# Main_DMB-4773-opto.net
KiCad netlist of a schematic drawn in EAGLE
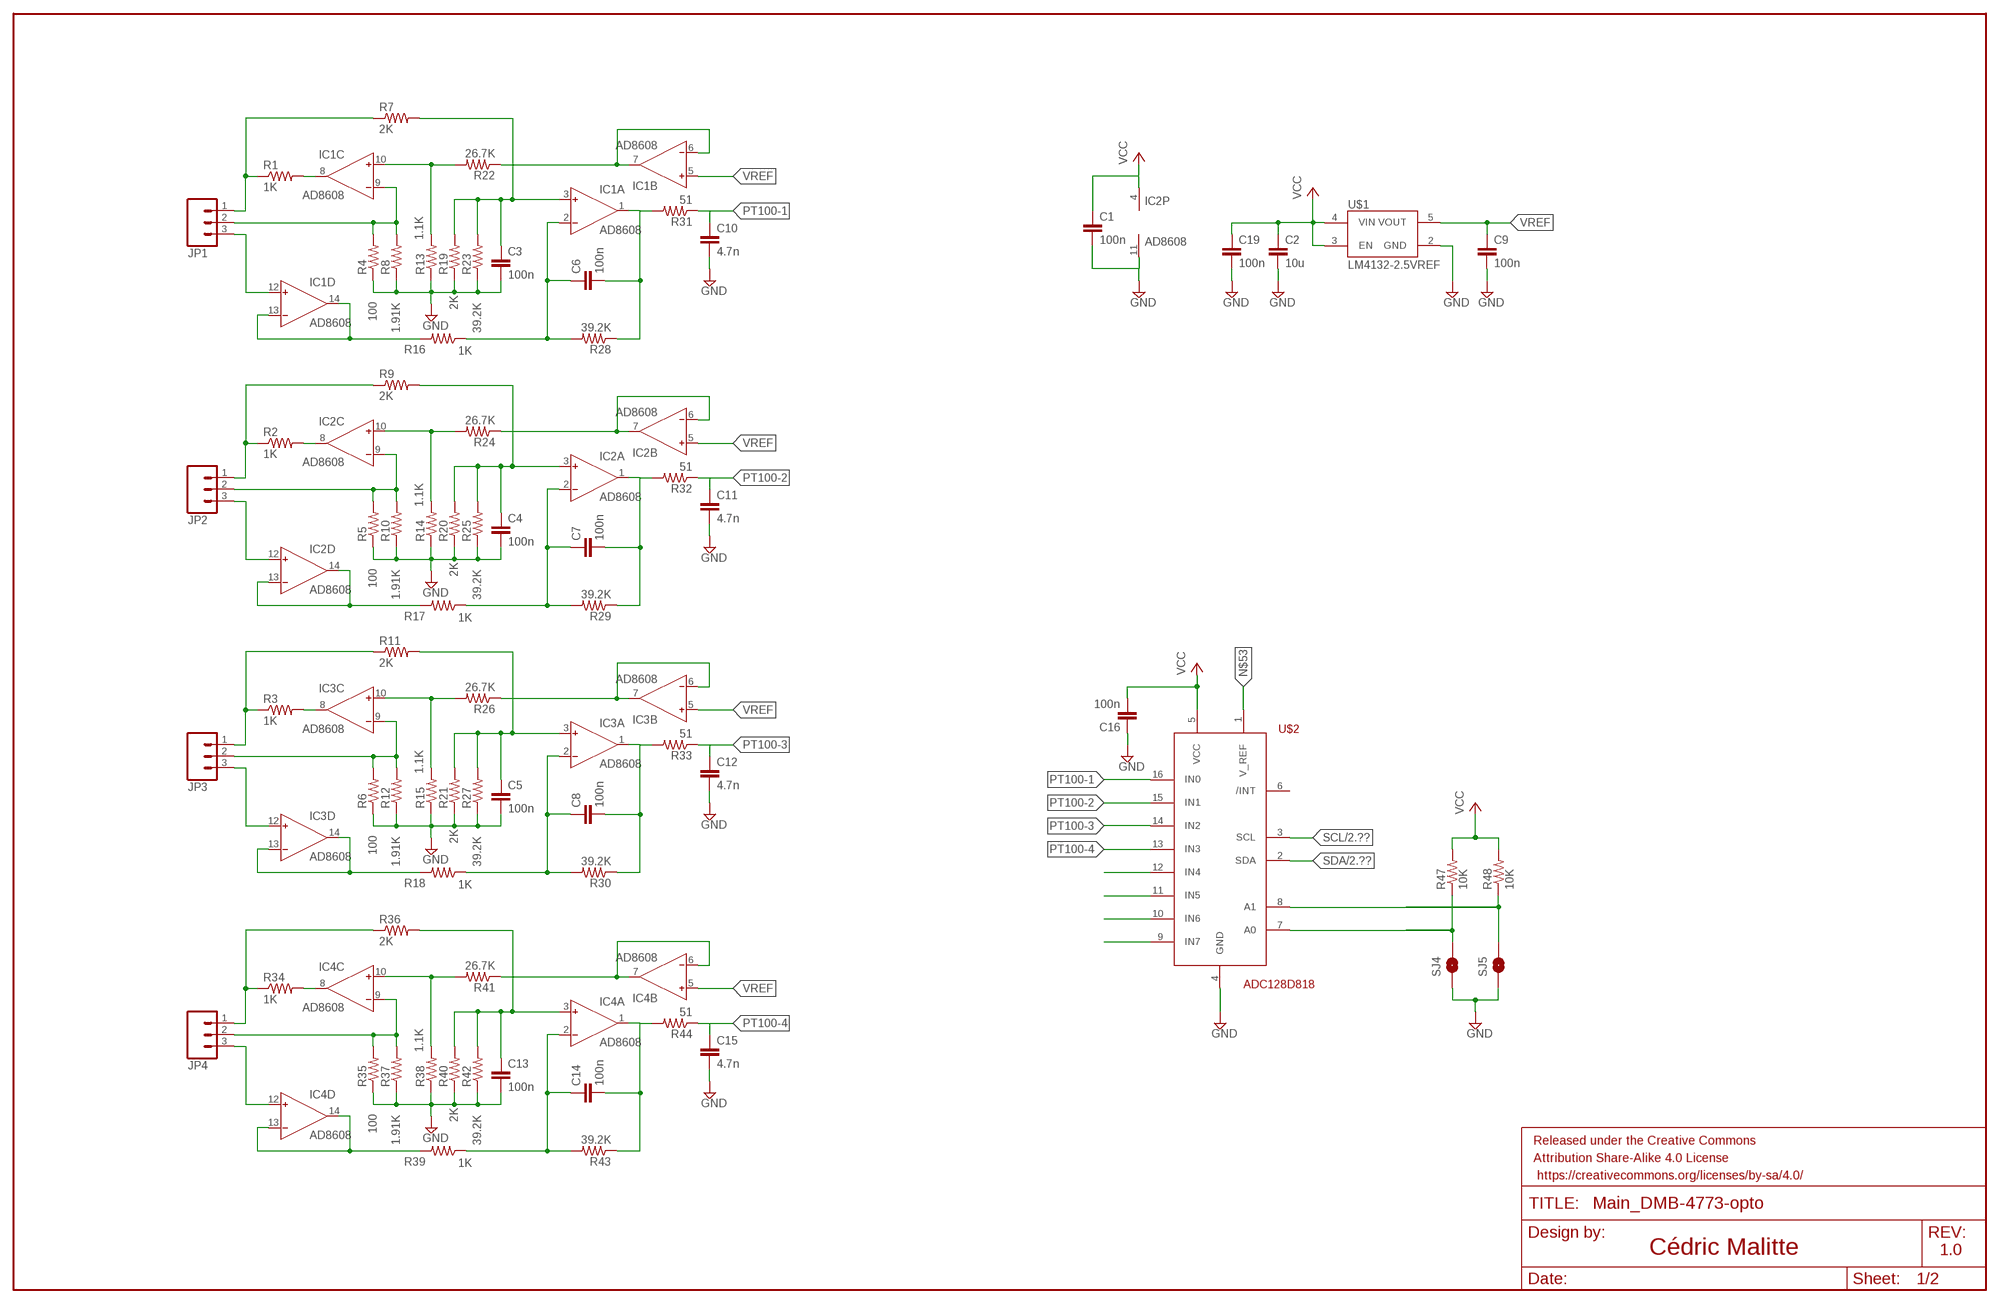
[diagram p0: schematic, sheet 1]
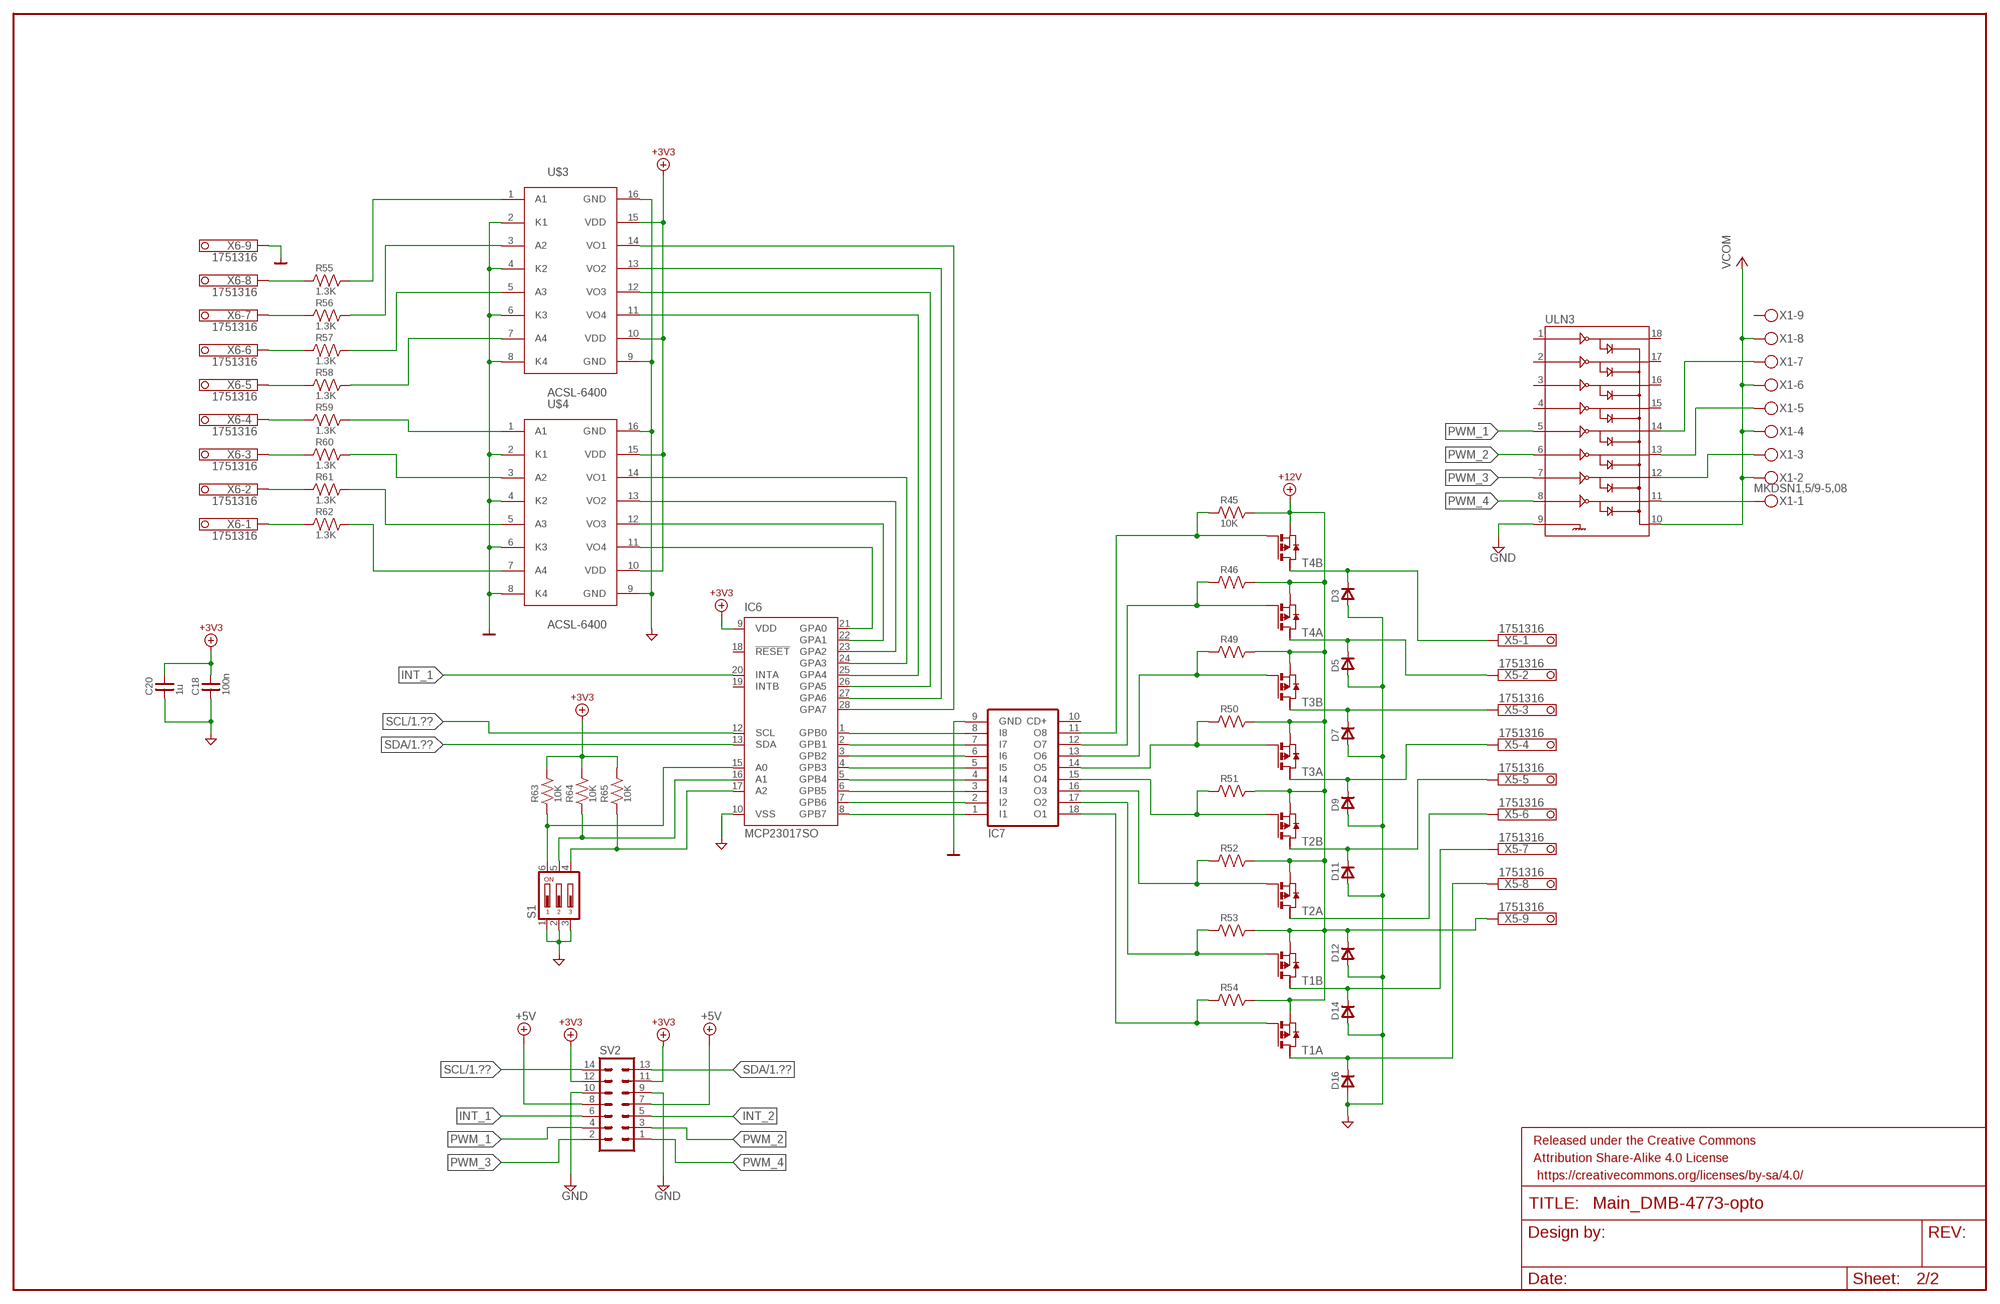
[diagram p1: schematic, sheet 2]

(export (version "E")
  (design (tool "Eeschema 10.0.6"))
  (components
    (comp (ref "C18")
      (value "100n")
      (footprint "eagle-import:C0805")
      (libsource (lib "eagle-import") (part "C0805"))
    )
    (comp (ref "C20")
      (value "1u")
      (footprint "eagle-import:C0805")
      (libsource (lib "eagle-import") (part "C0805"))
    )
    (comp (ref "D3")
      (value "DSMA")
      (footprint "eagle-import:DSMA")
      (libsource (lib "eagle-import") (part "DSMA"))
    )
    (comp (ref "D5")
      (value "DSMA")
      (footprint "eagle-import:DSMA")
      (libsource (lib "eagle-import") (part "DSMA"))
    )
    (comp (ref "D7")
      (value "DSMA")
      (footprint "eagle-import:DSMA")
      (libsource (lib "eagle-import") (part "DSMA"))
    )
    (comp (ref "D9")
      (value "DSMA")
      (footprint "eagle-import:DSMA")
      (libsource (lib "eagle-import") (part "DSMA"))
    )
    (comp (ref "D11")
      (value "DSMA")
      (footprint "eagle-import:DSMA")
      (libsource (lib "eagle-import") (part "DSMA"))
    )
    (comp (ref "D12")
      (value "DSMA")
      (footprint "eagle-import:DSMA")
      (libsource (lib "eagle-import") (part "DSMA"))
    )
    (comp (ref "D14")
      (value "DSMA")
      (footprint "eagle-import:DSMA")
      (libsource (lib "eagle-import") (part "DSMA"))
    )
    (comp (ref "D16")
      (value "DSMA")
      (footprint "eagle-import:DSMA")
      (libsource (lib "eagle-import") (part "DSMA"))
    )
    (comp (ref "FRAME3")
      (value "FRAME-LEDGER")
      (footprint "eagle-import:CREATIVE_COMMONS")
      (libsource (lib "eagle-import") (part "FRAME-LEDGER"))
    )
    (comp (ref "IC6")
      (value "MCP23017SO")
      (footprint "eagle-import:SO28W")
      (fields (field (name "MF") "MICROCHIP") (field (name "MPN") "MCP23017-E/SO"))
      (libsource (lib "eagle-import") (part "MCP23017SO"))
    )
    (comp (ref "IC7")
      (value "ULN2803A")
      (footprint "eagle-import:DIL18")
      (libsource (lib "eagle-import") (part "ULN2803A"))
    )
    (comp (ref "R45")
      (value "10K")
      (footprint "eagle-import:R0805")
      (libsource (lib "eagle-import") (part "RU0805"))
    )
    (comp (ref "R46")
      (value "RU0805")
      (footprint "eagle-import:R0805")
      (libsource (lib "eagle-import") (part "RU0805"))
    )
    (comp (ref "R49")
      (value "RU0805")
      (footprint "eagle-import:R0805")
      (libsource (lib "eagle-import") (part "RU0805"))
    )
    (comp (ref "R50")
      (value "RU0805")
      (footprint "eagle-import:R0805")
      (libsource (lib "eagle-import") (part "RU0805"))
    )
    (comp (ref "R51")
      (value "RU0805")
      (footprint "eagle-import:R0805")
      (libsource (lib "eagle-import") (part "RU0805"))
    )
    (comp (ref "R52")
      (value "RU0805")
      (footprint "eagle-import:R0805")
      (libsource (lib "eagle-import") (part "RU0805"))
    )
    (comp (ref "R53")
      (value "RU0805")
      (footprint "eagle-import:R0805")
      (libsource (lib "eagle-import") (part "RU0805"))
    )
    (comp (ref "R54")
      (value "RU0805")
      (footprint "eagle-import:R0805")
      (libsource (lib "eagle-import") (part "RU0805"))
    )
    (comp (ref "R55")
      (value "1.3K")
      (footprint "eagle-import:R0805")
      (libsource (lib "eagle-import") (part "RU0805"))
    )
    (comp (ref "R56")
      (value "1.3K")
      (footprint "eagle-import:R0805")
      (libsource (lib "eagle-import") (part "RU0805"))
    )
    (comp (ref "R57")
      (value "1.3K")
      (footprint "eagle-import:R0805")
      (libsource (lib "eagle-import") (part "RU0805"))
    )
    (comp (ref "R58")
      (value "1.3K")
      (footprint "eagle-import:R0805")
      (libsource (lib "eagle-import") (part "RU0805"))
    )
    (comp (ref "R59")
      (value "1.3K")
      (footprint "eagle-import:R0805")
      (libsource (lib "eagle-import") (part "RU0805"))
    )
    (comp (ref "R60")
      (value "1.3K")
      (footprint "eagle-import:R0805")
      (libsource (lib "eagle-import") (part "RU0805"))
    )
    (comp (ref "R61")
      (value "1.3K")
      (footprint "eagle-import:R0805")
      (libsource (lib "eagle-import") (part "RU0805"))
    )
    (comp (ref "R62")
      (value "1.3K")
      (footprint "eagle-import:R0805")
      (libsource (lib "eagle-import") (part "RU0805"))
    )
    (comp (ref "R63")
      (value "10K")
      (footprint "eagle-import:R0805")
      (libsource (lib "eagle-import") (part "RU0805"))
    )
    (comp (ref "R64")
      (value "10K")
      (footprint "eagle-import:R0805")
      (libsource (lib "eagle-import") (part "RU0805"))
    )
    (comp (ref "R65")
      (value "10K")
      (footprint "eagle-import:R0805")
      (libsource (lib "eagle-import") (part "RU0805"))
    )
    (comp (ref "S1")
      (value "DIP03YL")
      (footprint "eagle-import:DIP03YL")
      (libsource (lib "eagle-import") (part "DIP03YL"))
    )
    (comp (ref "SV2")
      (value "ML14")
      (footprint "eagle-import:ML14")
      (libsource (lib "eagle-import") (part "ML14"))
    )
    (comp (ref "T1")
      (value "PMOS2SO8")
      (footprint "eagle-import:SO8")
      (libsource (lib "eagle-import") (part "PMOS2SO8"))
    )
    (comp (ref "T2")
      (value "PMOS2SO8")
      (footprint "eagle-import:SO8")
      (libsource (lib "eagle-import") (part "PMOS2SO8"))
    )
    (comp (ref "T3")
      (value "PMOS2SO8")
      (footprint "eagle-import:SO8")
      (libsource (lib "eagle-import") (part "PMOS2SO8"))
    )
    (comp (ref "T4")
      (value "PMOS2SO8")
      (footprint "eagle-import:SO8")
      (libsource (lib "eagle-import") (part "PMOS2SO8"))
    )
    (comp (ref "U$3")
      (value "ACSL-6400")
      (footprint "eagle-import:SO16")
      (libsource (lib "eagle-import") (part "ACSL-6400"))
    )
    (comp (ref "U$4")
      (value "ACSL-6400")
      (footprint "eagle-import:SO16")
      (libsource (lib "eagle-import") (part "ACSL-6400"))
    )
    (comp (ref "ULN3")
      (value "ULN2803SOIC")
      (footprint "eagle-import:SO018")
      (libsource (lib "eagle-import") (part "ULN2803SOIC"))
    )
    (comp (ref "X1")
      (value "MKDSN1,5/9-5,08")
      (footprint "eagle-import:MKDSN1,5_9-5,08")
      (fields (field (name "MPN") "SMKDSN1,5/9-5,08"))
      (libsource (lib "eagle-import") (part "MKDSN1,5/9-5,08"))
    )
    (comp (ref "X5")
      (value "1751316")
      (footprint "eagle-import:1751316")
      (libsource (lib "eagle-import") (part "1751316"))
    )
    (comp (ref "X6")
      (value "1751316")
      (footprint "eagle-import:1751316")
      (libsource (lib "eagle-import") (part "1751316"))
    )
    (comp (ref "C1")
      (value "100n")
      (footprint "eagle-import:0805")
      (libsource (lib "eagle-import") (part "CAP0805"))
    )
    (comp (ref "C2")
      (value "10u")
      (footprint "eagle-import:0805")
      (libsource (lib "eagle-import") (part "CAP0805"))
    )
    (comp (ref "C3")
      (value "100n")
      (footprint "eagle-import:0805")
      (libsource (lib "eagle-import") (part "CAP0805"))
    )
    (comp (ref "C4")
      (value "100n")
      (footprint "eagle-import:0805")
      (libsource (lib "eagle-import") (part "CAP0805"))
    )
    (comp (ref "C5")
      (value "100n")
      (footprint "eagle-import:0805")
      (libsource (lib "eagle-import") (part "CAP0805"))
    )
    (comp (ref "C6")
      (value "100n")
      (footprint "eagle-import:0805")
      (libsource (lib "eagle-import") (part "CAP0805"))
    )
    (comp (ref "C7")
      (value "100n")
      (footprint "eagle-import:0805")
      (libsource (lib "eagle-import") (part "CAP0805"))
    )
    (comp (ref "C8")
      (value "100n")
      (footprint "eagle-import:0805")
      (libsource (lib "eagle-import") (part "CAP0805"))
    )
    (comp (ref "C9")
      (value "100n")
      (footprint "eagle-import:0805")
      (libsource (lib "eagle-import") (part "CAP0805"))
    )
    (comp (ref "C10")
      (value "4.7n")
      (footprint "eagle-import:0805")
      (libsource (lib "eagle-import") (part "CAP0805"))
    )
    (comp (ref "C11")
      (value "4.7n")
      (footprint "eagle-import:0805")
      (libsource (lib "eagle-import") (part "CAP0805"))
    )
    (comp (ref "C12")
      (value "4.7n")
      (footprint "eagle-import:0805")
      (libsource (lib "eagle-import") (part "CAP0805"))
    )
    (comp (ref "C13")
      (value "100n")
      (footprint "eagle-import:0805")
      (libsource (lib "eagle-import") (part "CAP0805"))
    )
    (comp (ref "C14")
      (value "100n")
      (footprint "eagle-import:0805")
      (libsource (lib "eagle-import") (part "CAP0805"))
    )
    (comp (ref "C15")
      (value "4.7n")
      (footprint "eagle-import:0805")
      (libsource (lib "eagle-import") (part "CAP0805"))
    )
    (comp (ref "C16")
      (value "100n")
      (footprint "eagle-import:0805")
      (libsource (lib "eagle-import") (part "CAP0805"))
    )
    (comp (ref "C19")
      (value "100n")
      (footprint "eagle-import:0805")
      (libsource (lib "eagle-import") (part "CAP0805"))
    )
    (comp (ref "FRAME1")
      (value "FRAME-LEDGER")
      (footprint "eagle-import:CREATIVE_COMMONS")
      (libsource (lib "eagle-import") (part "FRAME-LEDGER"))
    )
    (comp (ref "IC1")
      (value "AD8608")
      (footprint "eagle-import:SO14")
      (fields (field (name "MPN") "AD8609ARZ"))
      (libsource (lib "eagle-import") (part "AD8609R"))
    )
    (comp (ref "IC2")
      (value "AD8608")
      (footprint "eagle-import:SO14")
      (fields (field (name "MPN") "AD8609ARZ"))
      (libsource (lib "eagle-import") (part "AD8609R"))
    )
    (comp (ref "IC3")
      (value "AD8608")
      (footprint "eagle-import:SO14")
      (fields (field (name "MPN") "AD8609ARZ"))
      (libsource (lib "eagle-import") (part "AD8609R"))
    )
    (comp (ref "IC4")
      (value "AD8608")
      (footprint "eagle-import:SO14")
      (fields (field (name "MPN") "AD8609ARZ"))
      (libsource (lib "eagle-import") (part "AD8609R"))
    )
    (comp (ref "JP1")
      (value "M03SCREW")
      (footprint "eagle-import:SCREWTERMINAL-3.5MM-3")
      (libsource (lib "eagle-import") (part "M03SCREW"))
    )
    (comp (ref "JP2")
      (value "M03SCREW")
      (footprint "eagle-import:SCREWTERMINAL-3.5MM-3")
      (libsource (lib "eagle-import") (part "M03SCREW"))
    )
    (comp (ref "JP3")
      (value "M03SCREW")
      (footprint "eagle-import:SCREWTERMINAL-3.5MM-3")
      (libsource (lib "eagle-import") (part "M03SCREW"))
    )
    (comp (ref "JP4")
      (value "M03SCREW")
      (footprint "eagle-import:SCREWTERMINAL-3.5MM-3")
      (libsource (lib "eagle-import") (part "M03SCREW"))
    )
    (comp (ref "R1")
      (value "1K")
      (footprint "eagle-import:0805")
      (libsource (lib "eagle-import") (part "RESISTOR0805-RES"))
    )
    (comp (ref "R2")
      (value "1K")
      (footprint "eagle-import:0805")
      (libsource (lib "eagle-import") (part "RESISTOR0805-RES"))
    )
    (comp (ref "R3")
      (value "1K")
      (footprint "eagle-import:0805")
      (libsource (lib "eagle-import") (part "RESISTOR0805-RES"))
    )
    (comp (ref "R4")
      (value "100")
      (footprint "eagle-import:0805")
      (libsource (lib "eagle-import") (part "RESISTOR0805-RES"))
    )
    (comp (ref "R5")
      (value "100")
      (footprint "eagle-import:0805")
      (libsource (lib "eagle-import") (part "RESISTOR0805-RES"))
    )
    (comp (ref "R6")
      (value "100")
      (footprint "eagle-import:0805")
      (libsource (lib "eagle-import") (part "RESISTOR0805-RES"))
    )
    (comp (ref "R7")
      (value "2K")
      (footprint "eagle-import:0805")
      (libsource (lib "eagle-import") (part "RESISTOR0805-RES"))
    )
    (comp (ref "R8")
      (value "1.91K")
      (footprint "eagle-import:0805")
      (libsource (lib "eagle-import") (part "RESISTOR0805-RES"))
    )
    (comp (ref "R9")
      (value "2K")
      (footprint "eagle-import:0805")
      (libsource (lib "eagle-import") (part "RESISTOR0805-RES"))
    )
    (comp (ref "R10")
      (value "1.91K")
      (footprint "eagle-import:0805")
      (libsource (lib "eagle-import") (part "RESISTOR0805-RES"))
    )
    (comp (ref "R11")
      (value "2K")
      (footprint "eagle-import:0805")
      (libsource (lib "eagle-import") (part "RESISTOR0805-RES"))
    )
    (comp (ref "R12")
      (value "1.91K")
      (footprint "eagle-import:0805")
      (libsource (lib "eagle-import") (part "RESISTOR0805-RES"))
    )
    (comp (ref "R13")
      (value "1.1K")
      (footprint "eagle-import:0805")
      (libsource (lib "eagle-import") (part "RESISTOR0805-RES"))
    )
    (comp (ref "R14")
      (value "1.1K")
      (footprint "eagle-import:0805")
      (libsource (lib "eagle-import") (part "RESISTOR0805-RES"))
    )
    (comp (ref "R15")
      (value "1.1K")
      (footprint "eagle-import:0805")
      (libsource (lib "eagle-import") (part "RESISTOR0805-RES"))
    )
    (comp (ref "R16")
      (value "1K")
      (footprint "eagle-import:0805")
      (libsource (lib "eagle-import") (part "RESISTOR0805-RES"))
    )
    (comp (ref "R17")
      (value "1K")
      (footprint "eagle-import:0805")
      (libsource (lib "eagle-import") (part "RESISTOR0805-RES"))
    )
    (comp (ref "R18")
      (value "1K")
      (footprint "eagle-import:0805")
      (libsource (lib "eagle-import") (part "RESISTOR0805-RES"))
    )
    (comp (ref "R19")
      (value "2K")
      (footprint "eagle-import:0805")
      (libsource (lib "eagle-import") (part "RESISTOR0805-RES"))
    )
    (comp (ref "R20")
      (value "2K")
      (footprint "eagle-import:0805")
      (libsource (lib "eagle-import") (part "RESISTOR0805-RES"))
    )
    (comp (ref "R21")
      (value "2K")
      (footprint "eagle-import:0805")
      (libsource (lib "eagle-import") (part "RESISTOR0805-RES"))
    )
    (comp (ref "R22")
      (value "26.7K")
      (footprint "eagle-import:0805")
      (libsource (lib "eagle-import") (part "RESISTOR0805-RES"))
    )
    (comp (ref "R23")
      (value "39.2K")
      (footprint "eagle-import:0805")
      (libsource (lib "eagle-import") (part "RESISTOR0805-RES"))
    )
    (comp (ref "R24")
      (value "26.7K")
      (footprint "eagle-import:0805")
      (libsource (lib "eagle-import") (part "RESISTOR0805-RES"))
    )
    (comp (ref "R25")
      (value "39.2K")
      (footprint "eagle-import:0805")
      (libsource (lib "eagle-import") (part "RESISTOR0805-RES"))
    )
    (comp (ref "R26")
      (value "26.7K")
      (footprint "eagle-import:0805")
      (libsource (lib "eagle-import") (part "RESISTOR0805-RES"))
    )
    (comp (ref "R27")
      (value "39.2K")
      (footprint "eagle-import:0805")
      (libsource (lib "eagle-import") (part "RESISTOR0805-RES"))
    )
    (comp (ref "R28")
      (value "39.2K")
      (footprint "eagle-import:0805")
      (libsource (lib "eagle-import") (part "RESISTOR0805-RES"))
    )
    (comp (ref "R29")
      (value "39.2K")
      (footprint "eagle-import:0805")
      (libsource (lib "eagle-import") (part "RESISTOR0805-RES"))
    )
    (comp (ref "R30")
      (value "39.2K")
      (footprint "eagle-import:0805")
      (libsource (lib "eagle-import") (part "RESISTOR0805-RES"))
    )
    (comp (ref "R31")
      (value "51")
      (footprint "eagle-import:0805")
      (libsource (lib "eagle-import") (part "RESISTOR0805-RES"))
    )
    (comp (ref "R32")
      (value "51")
      (footprint "eagle-import:0805")
      (libsource (lib "eagle-import") (part "RESISTOR0805-RES"))
    )
    (comp (ref "R33")
      (value "51")
      (footprint "eagle-import:0805")
      (libsource (lib "eagle-import") (part "RESISTOR0805-RES"))
    )
    (comp (ref "R34")
      (value "1K")
      (footprint "eagle-import:0805")
      (libsource (lib "eagle-import") (part "RESISTOR0805-RES"))
    )
    (comp (ref "R35")
      (value "100")
      (footprint "eagle-import:0805")
      (libsource (lib "eagle-import") (part "RESISTOR0805-RES"))
    )
    (comp (ref "R36")
      (value "2K")
      (footprint "eagle-import:0805")
      (libsource (lib "eagle-import") (part "RESISTOR0805-RES"))
    )
    (comp (ref "R37")
      (value "1.91K")
      (footprint "eagle-import:0805")
      (libsource (lib "eagle-import") (part "RESISTOR0805-RES"))
    )
    (comp (ref "R38")
      (value "1.1K")
      (footprint "eagle-import:0805")
      (libsource (lib "eagle-import") (part "RESISTOR0805-RES"))
    )
    (comp (ref "R39")
      (value "1K")
      (footprint "eagle-import:0805")
      (libsource (lib "eagle-import") (part "RESISTOR0805-RES"))
    )
    (comp (ref "R40")
      (value "2K")
      (footprint "eagle-import:0805")
      (libsource (lib "eagle-import") (part "RESISTOR0805-RES"))
    )
    (comp (ref "R41")
      (value "26.7K")
      (footprint "eagle-import:0805")
      (libsource (lib "eagle-import") (part "RESISTOR0805-RES"))
    )
    (comp (ref "R42")
      (value "39.2K")
      (footprint "eagle-import:0805")
      (libsource (lib "eagle-import") (part "RESISTOR0805-RES"))
    )
    (comp (ref "R43")
      (value "39.2K")
      (footprint "eagle-import:0805")
      (libsource (lib "eagle-import") (part "RESISTOR0805-RES"))
    )
    (comp (ref "R44")
      (value "51")
      (footprint "eagle-import:0805")
      (libsource (lib "eagle-import") (part "RESISTOR0805-RES"))
    )
    (comp (ref "R47")
      (value "10K")
      (footprint "eagle-import:0805")
      (libsource (lib "eagle-import") (part "RESISTOR0805-RES"))
    )
    (comp (ref "R48")
      (value "10K")
      (footprint "eagle-import:0805")
      (libsource (lib "eagle-import") (part "RESISTOR0805-RES"))
    )
    (comp (ref "SJ4")
      (value "SOLDERJUMPERNC")
      (footprint "eagle-import:SJ_2S")
      (libsource (lib "eagle-import") (part "SOLDERJUMPERNC"))
    )
    (comp (ref "SJ5")
      (value "SOLDERJUMPERNC")
      (footprint "eagle-import:SJ_2S")
      (libsource (lib "eagle-import") (part "SOLDERJUMPERNC"))
    )
    (comp (ref "U$1")
      (value "LM4132-2.5VREF")
      (footprint "eagle-import:SOT23-5")
      (libsource (lib "eagle-import") (part "LM4128-2.5VREF"))
    )
    (comp (ref "U$2")
      (value "ADC128D818")
      (footprint "eagle-import:SSOP16")
      (libsource (lib "eagle-import") (part "ADC128D818"))
    )
  )
  (nets
    (net (code "1") (name "+3V3") (class "Default")
      (node (ref "C18") (pin "2") (pinfunction "2_2") (pintype "passive"))
      (node (ref "C20") (pin "2") (pinfunction "2_2") (pintype "passive"))
      (node (ref "IC6") (pin "9") (pinfunction "VDD_9") (pintype "power_in"))
      (node (ref "R63") (pin "2") (pinfunction "2_2") (pintype "passive"))
      (node (ref "R64") (pin "2") (pinfunction "2_2") (pintype "passive"))
      (node (ref "R65") (pin "2") (pinfunction "2_2") (pintype "passive"))
      (node (ref "SV2") (pin "11") (pinfunction "11_11") (pintype "passive"))
      (node (ref "SV2") (pin "12") (pinfunction "12_12") (pintype "passive"))
      (node (ref "U$3") (pin "10") (pinfunction "VDD_10") (pintype "power_in"))
      (node (ref "U$3") (pin "15") (pinfunction "VDD_15") (pintype "power_in"))
      (node (ref "U$4") (pin "10") (pinfunction "VDD_10") (pintype "power_in"))
      (node (ref "U$4") (pin "15") (pinfunction "VDD_15") (pintype "power_in"))
    )
    (net (code "2") (name "+5V") (class "Default")
      (node (ref "SV2") (pin "7") (pinfunction "7_7") (pintype "passive"))
      (node (ref "SV2") (pin "8") (pinfunction "8_8") (pintype "passive"))
    )
    (net (code "3") (name "DGND") (class "Default")
      (node (ref "C18") (pin "1") (pinfunction "1_1") (pintype "passive"))
      (node (ref "C20") (pin "1") (pinfunction "1_1") (pintype "passive"))
      (node (ref "D11") (pin "A") (pinfunction "A_A") (pintype "passive"))
      (node (ref "D12") (pin "A") (pinfunction "A_A") (pintype "passive"))
      (node (ref "D14") (pin "A") (pinfunction "A_A") (pintype "passive"))
      (node (ref "D16") (pin "A") (pinfunction "A_A") (pintype "passive"))
      (node (ref "D3") (pin "A") (pinfunction "A_A") (pintype "passive"))
      (node (ref "D5") (pin "A") (pinfunction "A_A") (pintype "passive"))
      (node (ref "D7") (pin "A") (pinfunction "A_A") (pintype "passive"))
      (node (ref "D9") (pin "A") (pinfunction "A_A") (pintype "passive"))
      (node (ref "IC6") (pin "10") (pinfunction "VSS_10") (pintype "power_in"))
      (node (ref "S1") (pin "1") (pinfunction "1_1") (pintype "passive"))
      (node (ref "S1") (pin "2") (pinfunction "2_2") (pintype "passive"))
      (node (ref "S1") (pin "3") (pinfunction "3_3") (pintype "passive"))
      (node (ref "U$3") (pin "16") (pinfunction "GND_16") (pintype "power_in"))
      (node (ref "U$3") (pin "9") (pinfunction "GND_9") (pintype "power_in"))
      (node (ref "U$4") (pin "16") (pinfunction "GND_16") (pintype "power_in"))
      (node (ref "U$4") (pin "9") (pinfunction "GND_9") (pintype "power_in"))
    )
    (net (code "4") (name "GND") (class "Default")
      (node (ref "C1") (pin "2") (pinfunction "2_2") (pintype "passive"))
      (node (ref "C10") (pin "2") (pinfunction "2_2") (pintype "passive"))
      (node (ref "C11") (pin "2") (pinfunction "2_2") (pintype "passive"))
      (node (ref "C12") (pin "2") (pinfunction "2_2") (pintype "passive"))
      (node (ref "C13") (pin "2") (pinfunction "2_2") (pintype "passive"))
      (node (ref "C15") (pin "2") (pinfunction "2_2") (pintype "passive"))
      (node (ref "C16") (pin "1") (pinfunction "1_1") (pintype "passive"))
      (node (ref "C19") (pin "2") (pinfunction "2_2") (pintype "passive"))
      (node (ref "C2") (pin "2") (pinfunction "2_2") (pintype "passive"))
      (node (ref "C3") (pin "2") (pinfunction "2_2") (pintype "passive"))
      (node (ref "C4") (pin "2") (pinfunction "2_2") (pintype "passive"))
      (node (ref "C5") (pin "2") (pinfunction "2_2") (pintype "passive"))
      (node (ref "C9") (pin "2") (pinfunction "2_2") (pintype "passive"))
      (node (ref "IC2") (pin "11") (pinfunction "V-_11") (pintype "power_in"))
      (node (ref "IC7") (pin "9") (pinfunction "GND_9") (pintype "power_in"))
      (node (ref "R10") (pin "1") (pinfunction "1_1") (pintype "passive"))
      (node (ref "R12") (pin "1") (pinfunction "1_1") (pintype "passive"))
      (node (ref "R13") (pin "1") (pinfunction "1_1") (pintype "passive"))
      (node (ref "R14") (pin "1") (pinfunction "1_1") (pintype "passive"))
      (node (ref "R15") (pin "1") (pinfunction "1_1") (pintype "passive"))
      (node (ref "R19") (pin "1") (pinfunction "1_1") (pintype "passive"))
      (node (ref "R20") (pin "1") (pinfunction "1_1") (pintype "passive"))
      (node (ref "R21") (pin "1") (pinfunction "1_1") (pintype "passive"))
      (node (ref "R23") (pin "1") (pinfunction "1_1") (pintype "passive"))
      (node (ref "R25") (pin "1") (pinfunction "1_1") (pintype "passive"))
      (node (ref "R27") (pin "1") (pinfunction "1_1") (pintype "passive"))
      (node (ref "R35") (pin "1") (pinfunction "1_1") (pintype "passive"))
      (node (ref "R37") (pin "1") (pinfunction "1_1") (pintype "passive"))
      (node (ref "R38") (pin "1") (pinfunction "1_1") (pintype "passive"))
      (node (ref "R4") (pin "1") (pinfunction "1_1") (pintype "passive"))
      (node (ref "R40") (pin "1") (pinfunction "1_1") (pintype "passive"))
      (node (ref "R42") (pin "1") (pinfunction "1_1") (pintype "passive"))
      (node (ref "R5") (pin "1") (pinfunction "1_1") (pintype "passive"))
      (node (ref "R6") (pin "1") (pinfunction "1_1") (pintype "passive"))
      (node (ref "R8") (pin "1") (pinfunction "1_1") (pintype "passive"))
      (node (ref "SJ4") (pin "1") (pinfunction "1_1") (pintype "passive"))
      (node (ref "SJ5") (pin "1") (pinfunction "1_1") (pintype "passive"))
      (node (ref "SV2") (pin "10") (pinfunction "10_10") (pintype "passive"))
      (node (ref "SV2") (pin "9") (pinfunction "9_9") (pintype "passive"))
      (node (ref "U$1") (pin "2") (pinfunction "GND_2") (pintype "bidirectional"))
      (node (ref "U$2") (pin "4") (pinfunction "GND_4") (pintype "power_in"))
      (node (ref "U$3") (pin "2") (pinfunction "K1_2") (pintype "input"))
      (node (ref "U$3") (pin "4") (pinfunction "K2_4") (pintype "input"))
      (node (ref "U$3") (pin "6") (pinfunction "K3_6") (pintype "input"))
      (node (ref "U$3") (pin "8") (pinfunction "K4_8") (pintype "input"))
      (node (ref "U$4") (pin "2") (pinfunction "K1_2") (pintype "input"))
      (node (ref "U$4") (pin "4") (pinfunction "K2_4") (pintype "input"))
      (node (ref "U$4") (pin "6") (pinfunction "K3_6") (pintype "input"))
      (node (ref "U$4") (pin "8") (pinfunction "K4_8") (pintype "input"))
      (node (ref "ULN3") (pin "9") (pinfunction "9_9") (pintype "bidirectional"))
      (node (ref "X6") (pin "9") (pinfunction "K_9") (pintype "passive"))
    )
    (net (code "5") (name "INT_1") (class "Default")
      (node (ref "IC6") (pin "20") (pinfunction "INTA_20") (pintype "output"))
      (node (ref "SV2") (pin "6") (pinfunction "6_6") (pintype "passive"))
    )
    (net (code "6") (name "INT_2") (class "Default")
      (node (ref "SV2") (pin "5") (pinfunction "5_5") (pintype "passive"))
    )
    (net (code "7") (name "N$53") (class "Default")
      (node (ref "U$2") (pin "1") (pinfunction "V_REF_1") (pintype "input"))
    )
    (net (code "8") (name "Net-(IC1A-IN+)") (class "Default")
      (node (ref "C3") (pin "1") (pinfunction "1_1") (pintype "passive"))
      (node (ref "IC1") (pin "3") (pinfunction "IN+_3") (pintype "input"))
      (node (ref "R19") (pin "2") (pinfunction "2_2") (pintype "passive"))
      (node (ref "R23") (pin "2") (pinfunction "2_2") (pintype "passive"))
      (node (ref "R7") (pin "2") (pinfunction "2_2") (pintype "passive"))
    )
    (net (code "9") (name "Net-(IC1A-IN-)") (class "Default")
      (node (ref "C6") (pin "1") (pinfunction "1_1") (pintype "passive"))
      (node (ref "IC1") (pin "2") (pinfunction "IN-_2") (pintype "input"))
      (node (ref "R16") (pin "1") (pinfunction "1_1") (pintype "passive"))
      (node (ref "R28") (pin "2") (pinfunction "2_2") (pintype "passive"))
    )
    (net (code "10") (name "Net-(IC1A-OUT)") (class "Default")
      (node (ref "C6") (pin "2") (pinfunction "2_2") (pintype "passive"))
      (node (ref "IC1") (pin "1") (pinfunction "OUT_1") (pintype "output"))
      (node (ref "R28") (pin "1") (pinfunction "1_1") (pintype "passive"))
      (node (ref "R31") (pin "2") (pinfunction "2_2") (pintype "passive"))
    )
    (net (code "11") (name "Net-(IC1B-IN-)") (class "Default")
      (node (ref "IC1") (pin "6") (pinfunction "IN-_6") (pintype "input"))
      (node (ref "IC1") (pin "7") (pinfunction "OUT_7") (pintype "output"))
      (node (ref "R22") (pin "1") (pinfunction "1_1") (pintype "passive"))
    )
    (net (code "12") (name "Net-(IC1C-IN+)") (class "Default")
      (node (ref "IC1") (pin "10") (pinfunction "IN+_10") (pintype "input"))
      (node (ref "R13") (pin "2") (pinfunction "2_2") (pintype "passive"))
      (node (ref "R22") (pin "2") (pinfunction "2_2") (pintype "passive"))
    )
    (net (code "13") (name "Net-(IC1C-IN-)") (class "Default")
      (node (ref "IC1") (pin "9") (pinfunction "IN-_9") (pintype "input"))
      (node (ref "JP1") (pin "2") (pinfunction "2_2") (pintype "passive"))
      (node (ref "R4") (pin "2") (pinfunction "2_2") (pintype "passive"))
      (node (ref "R8") (pin "2") (pinfunction "2_2") (pintype "passive"))
    )
    (net (code "14") (name "Net-(IC1C-OUT)") (class "Default")
      (node (ref "IC1") (pin "8") (pinfunction "OUT_8") (pintype "output"))
      (node (ref "R1") (pin "2") (pinfunction "2_2") (pintype "passive"))
    )
    (net (code "15") (name "Net-(IC1D-IN+)") (class "Default")
      (node (ref "IC1") (pin "12") (pinfunction "IN+_12") (pintype "input"))
      (node (ref "JP1") (pin "3") (pinfunction "3_3") (pintype "passive"))
    )
    (net (code "16") (name "Net-(IC1D-IN-)") (class "Default")
      (node (ref "IC1") (pin "13") (pinfunction "IN-_13") (pintype "input"))
      (node (ref "IC1") (pin "14") (pinfunction "OUT_14") (pintype "output"))
      (node (ref "R16") (pin "2") (pinfunction "2_2") (pintype "passive"))
    )
    (net (code "17") (name "Net-(IC2A-IN+)") (class "Default")
      (node (ref "C4") (pin "1") (pinfunction "1_1") (pintype "passive"))
      (node (ref "IC2") (pin "3") (pinfunction "IN+_3") (pintype "input"))
      (node (ref "R20") (pin "2") (pinfunction "2_2") (pintype "passive"))
      (node (ref "R25") (pin "2") (pinfunction "2_2") (pintype "passive"))
      (node (ref "R9") (pin "2") (pinfunction "2_2") (pintype "passive"))
    )
    (net (code "18") (name "Net-(IC2A-IN-)") (class "Default")
      (node (ref "C7") (pin "1") (pinfunction "1_1") (pintype "passive"))
      (node (ref "IC2") (pin "2") (pinfunction "IN-_2") (pintype "input"))
      (node (ref "R17") (pin "1") (pinfunction "1_1") (pintype "passive"))
      (node (ref "R29") (pin "2") (pinfunction "2_2") (pintype "passive"))
    )
    (net (code "19") (name "Net-(IC2A-OUT)") (class "Default")
      (node (ref "C7") (pin "2") (pinfunction "2_2") (pintype "passive"))
      (node (ref "IC2") (pin "1") (pinfunction "OUT_1") (pintype "output"))
      (node (ref "R29") (pin "1") (pinfunction "1_1") (pintype "passive"))
      (node (ref "R32") (pin "2") (pinfunction "2_2") (pintype "passive"))
    )
    (net (code "20") (name "Net-(IC2B-IN-)") (class "Default")
      (node (ref "IC2") (pin "6") (pinfunction "IN-_6") (pintype "input"))
      (node (ref "IC2") (pin "7") (pinfunction "OUT_7") (pintype "output"))
      (node (ref "R24") (pin "1") (pinfunction "1_1") (pintype "passive"))
    )
    (net (code "21") (name "Net-(IC2C-IN+)") (class "Default")
      (node (ref "IC2") (pin "10") (pinfunction "IN+_10") (pintype "input"))
      (node (ref "R14") (pin "2") (pinfunction "2_2") (pintype "passive"))
      (node (ref "R24") (pin "2") (pinfunction "2_2") (pintype "passive"))
    )
    (net (code "22") (name "Net-(IC2C-IN-)") (class "Default")
      (node (ref "IC2") (pin "9") (pinfunction "IN-_9") (pintype "input"))
      (node (ref "JP2") (pin "2") (pinfunction "2_2") (pintype "passive"))
      (node (ref "R10") (pin "2") (pinfunction "2_2") (pintype "passive"))
      (node (ref "R5") (pin "2") (pinfunction "2_2") (pintype "passive"))
    )
    (net (code "23") (name "Net-(IC2C-OUT)") (class "Default")
      (node (ref "IC2") (pin "8") (pinfunction "OUT_8") (pintype "output"))
      (node (ref "R2") (pin "2") (pinfunction "2_2") (pintype "passive"))
    )
    (net (code "24") (name "Net-(IC2D-IN+)") (class "Default")
      (node (ref "IC2") (pin "12") (pinfunction "IN+_12") (pintype "input"))
      (node (ref "JP2") (pin "3") (pinfunction "3_3") (pintype "passive"))
    )
    (net (code "25") (name "Net-(IC2D-IN-)") (class "Default")
      (node (ref "IC2") (pin "13") (pinfunction "IN-_13") (pintype "input"))
      (node (ref "IC2") (pin "14") (pinfunction "OUT_14") (pintype "output"))
      (node (ref "R17") (pin "2") (pinfunction "2_2") (pintype "passive"))
    )
    (net (code "26") (name "Net-(IC3A-IN+)") (class "Default")
      (node (ref "C5") (pin "1") (pinfunction "1_1") (pintype "passive"))
      (node (ref "IC3") (pin "3") (pinfunction "IN+_3") (pintype "input"))
      (node (ref "R11") (pin "2") (pinfunction "2_2") (pintype "passive"))
      (node (ref "R21") (pin "2") (pinfunction "2_2") (pintype "passive"))
      (node (ref "R27") (pin "2") (pinfunction "2_2") (pintype "passive"))
    )
    (net (code "27") (name "Net-(IC3A-IN-)") (class "Default")
      (node (ref "C8") (pin "1") (pinfunction "1_1") (pintype "passive"))
      (node (ref "IC3") (pin "2") (pinfunction "IN-_2") (pintype "input"))
      (node (ref "R18") (pin "1") (pinfunction "1_1") (pintype "passive"))
      (node (ref "R30") (pin "2") (pinfunction "2_2") (pintype "passive"))
    )
    (net (code "28") (name "Net-(IC3A-OUT)") (class "Default")
      (node (ref "C8") (pin "2") (pinfunction "2_2") (pintype "passive"))
      (node (ref "IC3") (pin "1") (pinfunction "OUT_1") (pintype "output"))
      (node (ref "R30") (pin "1") (pinfunction "1_1") (pintype "passive"))
      (node (ref "R33") (pin "2") (pinfunction "2_2") (pintype "passive"))
    )
    (net (code "29") (name "Net-(IC3B-IN-)") (class "Default")
      (node (ref "IC3") (pin "6") (pinfunction "IN-_6") (pintype "input"))
      (node (ref "IC3") (pin "7") (pinfunction "OUT_7") (pintype "output"))
      (node (ref "R26") (pin "1") (pinfunction "1_1") (pintype "passive"))
    )
    (net (code "30") (name "Net-(IC3C-IN+)") (class "Default")
      (node (ref "IC3") (pin "10") (pinfunction "IN+_10") (pintype "input"))
      (node (ref "R15") (pin "2") (pinfunction "2_2") (pintype "passive"))
      (node (ref "R26") (pin "2") (pinfunction "2_2") (pintype "passive"))
    )
    (net (code "31") (name "Net-(IC3C-IN-)") (class "Default")
      (node (ref "IC3") (pin "9") (pinfunction "IN-_9") (pintype "input"))
      (node (ref "JP3") (pin "2") (pinfunction "2_2") (pintype "passive"))
      (node (ref "R12") (pin "2") (pinfunction "2_2") (pintype "passive"))
      (node (ref "R6") (pin "2") (pinfunction "2_2") (pintype "passive"))
    )
    (net (code "32") (name "Net-(IC3C-OUT)") (class "Default")
      (node (ref "IC3") (pin "8") (pinfunction "OUT_8") (pintype "output"))
      (node (ref "R3") (pin "2") (pinfunction "2_2") (pintype "passive"))
    )
    (net (code "33") (name "Net-(IC3D-IN+)") (class "Default")
      (node (ref "IC3") (pin "12") (pinfunction "IN+_12") (pintype "input"))
      (node (ref "JP3") (pin "3") (pinfunction "3_3") (pintype "passive"))
    )
    (net (code "34") (name "Net-(IC3D-IN-)") (class "Default")
      (node (ref "IC3") (pin "13") (pinfunction "IN-_13") (pintype "input"))
      (node (ref "IC3") (pin "14") (pinfunction "OUT_14") (pintype "output"))
      (node (ref "R18") (pin "2") (pinfunction "2_2") (pintype "passive"))
    )
    (net (code "35") (name "Net-(IC4A-IN+)") (class "Default")
      (node (ref "C13") (pin "1") (pinfunction "1_1") (pintype "passive"))
      (node (ref "IC4") (pin "3") (pinfunction "IN+_3") (pintype "input"))
      (node (ref "R36") (pin "2") (pinfunction "2_2") (pintype "passive"))
      (node (ref "R40") (pin "2") (pinfunction "2_2") (pintype "passive"))
      (node (ref "R42") (pin "2") (pinfunction "2_2") (pintype "passive"))
    )
    (net (code "36") (name "Net-(IC4A-IN-)") (class "Default")
      (node (ref "C14") (pin "1") (pinfunction "1_1") (pintype "passive"))
      (node (ref "IC4") (pin "2") (pinfunction "IN-_2") (pintype "input"))
      (node (ref "R39") (pin "1") (pinfunction "1_1") (pintype "passive"))
      (node (ref "R43") (pin "2") (pinfunction "2_2") (pintype "passive"))
    )
    (net (code "37") (name "Net-(IC4A-OUT)") (class "Default")
      (node (ref "C14") (pin "2") (pinfunction "2_2") (pintype "passive"))
      (node (ref "IC4") (pin "1") (pinfunction "OUT_1") (pintype "output"))
      (node (ref "R43") (pin "1") (pinfunction "1_1") (pintype "passive"))
      (node (ref "R44") (pin "2") (pinfunction "2_2") (pintype "passive"))
    )
    (net (code "38") (name "Net-(IC4B-IN-)") (class "Default")
      (node (ref "IC4") (pin "6") (pinfunction "IN-_6") (pintype "input"))
      (node (ref "IC4") (pin "7") (pinfunction "OUT_7") (pintype "output"))
      (node (ref "R41") (pin "1") (pinfunction "1_1") (pintype "passive"))
    )
    (net (code "39") (name "Net-(IC4C-IN+)") (class "Default")
      (node (ref "IC4") (pin "10") (pinfunction "IN+_10") (pintype "input"))
      (node (ref "R38") (pin "2") (pinfunction "2_2") (pintype "passive"))
      (node (ref "R41") (pin "2") (pinfunction "2_2") (pintype "passive"))
    )
    (net (code "40") (name "Net-(IC4C-IN-)") (class "Default")
      (node (ref "IC4") (pin "9") (pinfunction "IN-_9") (pintype "input"))
      (node (ref "JP4") (pin "2") (pinfunction "2_2") (pintype "passive"))
      (node (ref "R35") (pin "2") (pinfunction "2_2") (pintype "passive"))
      (node (ref "R37") (pin "2") (pinfunction "2_2") (pintype "passive"))
    )
    (net (code "41") (name "Net-(IC4C-OUT)") (class "Default")
      (node (ref "IC4") (pin "8") (pinfunction "OUT_8") (pintype "output"))
      (node (ref "R34") (pin "2") (pinfunction "2_2") (pintype "passive"))
    )
    (net (code "42") (name "Net-(IC4D-IN+)") (class "Default")
      (node (ref "IC4") (pin "12") (pinfunction "IN+_12") (pintype "input"))
      (node (ref "JP4") (pin "3") (pinfunction "3_3") (pintype "passive"))
    )
    (net (code "43") (name "Net-(IC4D-IN-)") (class "Default")
      (node (ref "IC4") (pin "13") (pinfunction "IN-_13") (pintype "input"))
      (node (ref "IC4") (pin "14") (pinfunction "OUT_14") (pintype "output"))
      (node (ref "R39") (pin "2") (pinfunction "2_2") (pintype "passive"))
    )
    (net (code "44") (name "Net-(IC6-A0)") (class "Default")
      (node (ref "IC6") (pin "15") (pinfunction "A0_15") (pintype "input"))
      (node (ref "R63") (pin "1") (pinfunction "1_1") (pintype "passive"))
      (node (ref "S1") (pin "6") (pinfunction "6_6") (pintype "passive"))
    )
    (net (code "45") (name "Net-(IC6-A1)") (class "Default")
      (node (ref "IC6") (pin "16") (pinfunction "A1_16") (pintype "input"))
      (node (ref "R64") (pin "1") (pinfunction "1_1") (pintype "passive"))
      (node (ref "S1") (pin "5") (pinfunction "5_5") (pintype "passive"))
    )
    (net (code "46") (name "Net-(IC6-A2)") (class "Default")
      (node (ref "IC6") (pin "17") (pinfunction "A2_17") (pintype "input"))
      (node (ref "R65") (pin "1") (pinfunction "1_1") (pintype "passive"))
      (node (ref "S1") (pin "4") (pinfunction "4_4") (pintype "passive"))
    )
    (net (code "47") (name "Net-(IC6-GPA0)") (class "Default")
      (node (ref "IC6") (pin "21") (pinfunction "GPA0_21") (pintype "bidirectional"))
      (node (ref "U$4") (pin "11") (pinfunction "VO4_11") (pintype "bidirectional"))
    )
    (net (code "48") (name "Net-(IC6-GPA1)") (class "Default")
      (node (ref "IC6") (pin "22") (pinfunction "GPA1_22") (pintype "bidirectional"))
      (node (ref "U$4") (pin "12") (pinfunction "VO3_12") (pintype "bidirectional"))
    )
    (net (code "49") (name "Net-(IC6-GPA2)") (class "Default")
      (node (ref "IC6") (pin "23") (pinfunction "GPA2_23") (pintype "bidirectional"))
      (node (ref "U$4") (pin "13") (pinfunction "VO2_13") (pintype "bidirectional"))
    )
    (net (code "50") (name "Net-(IC6-GPA3)") (class "Default")
      (node (ref "IC6") (pin "24") (pinfunction "GPA3_24") (pintype "bidirectional"))
      (node (ref "U$4") (pin "14") (pinfunction "VO1_14") (pintype "bidirectional"))
    )
    (net (code "51") (name "Net-(IC6-GPA4)") (class "Default")
      (node (ref "IC6") (pin "25") (pinfunction "GPA4_25") (pintype "bidirectional"))
      (node (ref "U$3") (pin "11") (pinfunction "VO4_11") (pintype "bidirectional"))
    )
    (net (code "52") (name "Net-(IC6-GPA5)") (class "Default")
      (node (ref "IC6") (pin "26") (pinfunction "GPA5_26") (pintype "bidirectional"))
      (node (ref "U$3") (pin "12") (pinfunction "VO3_12") (pintype "bidirectional"))
    )
    (net (code "53") (name "Net-(IC6-GPA6)") (class "Default")
      (node (ref "IC6") (pin "27") (pinfunction "GPA6_27") (pintype "bidirectional"))
      (node (ref "U$3") (pin "13") (pinfunction "VO2_13") (pintype "bidirectional"))
    )
    (net (code "54") (name "Net-(IC6-GPA7)") (class "Default")
      (node (ref "IC6") (pin "28") (pinfunction "GPA7_28") (pintype "bidirectional"))
      (node (ref "U$3") (pin "14") (pinfunction "VO1_14") (pintype "bidirectional"))
    )
    (net (code "55") (name "Net-(IC6-GPB0)") (class "Default")
      (node (ref "IC6") (pin "1") (pinfunction "GPB0_1") (pintype "bidirectional"))
      (node (ref "IC7") (pin "8") (pinfunction "I8_8") (pintype "input"))
    )
    (net (code "56") (name "Net-(IC6-GPB1)") (class "Default")
      (node (ref "IC6") (pin "2") (pinfunction "GPB1_2") (pintype "bidirectional"))
      (node (ref "IC7") (pin "7") (pinfunction "I7_7") (pintype "input"))
    )
    (net (code "57") (name "Net-(IC6-GPB2)") (class "Default")
      (node (ref "IC6") (pin "3") (pinfunction "GPB2_3") (pintype "bidirectional"))
      (node (ref "IC7") (pin "6") (pinfunction "I6_6") (pintype "input"))
    )
    (net (code "58") (name "Net-(IC6-GPB3)") (class "Default")
      (node (ref "IC6") (pin "4") (pinfunction "GPB3_4") (pintype "bidirectional"))
      (node (ref "IC7") (pin "5") (pinfunction "I5_5") (pintype "input"))
    )
    (net (code "59") (name "Net-(IC6-GPB4)") (class "Default")
      (node (ref "IC6") (pin "5") (pinfunction "GPB4_5") (pintype "bidirectional"))
      (node (ref "IC7") (pin "4") (pinfunction "I4_4") (pintype "input"))
    )
    (net (code "60") (name "Net-(IC6-GPB5)") (class "Default")
      (node (ref "IC6") (pin "6") (pinfunction "GPB5_6") (pintype "bidirectional"))
      (node (ref "IC7") (pin "3") (pinfunction "I3_3") (pintype "input"))
    )
    (net (code "61") (name "Net-(IC6-GPB6)") (class "Default")
      (node (ref "IC6") (pin "7") (pinfunction "GPB6_7") (pintype "bidirectional"))
      (node (ref "IC7") (pin "2") (pinfunction "I2_2") (pintype "input"))
    )
    (net (code "62") (name "Net-(IC6-GPB7)") (class "Default")
      (node (ref "IC6") (pin "8") (pinfunction "GPB7_8") (pintype "bidirectional"))
      (node (ref "IC7") (pin "1") (pinfunction "I1_1") (pintype "input"))
    )
    (net (code "63") (name "Net-(IC7-O1)") (class "Default")
      (node (ref "IC7") (pin "18") (pinfunction "O1_18") (pintype "open_collector"))
      (node (ref "R54") (pin "1") (pinfunction "1_1") (pintype "passive"))
      (node (ref "T1") (pin "2") (pinfunction "G_2") (pintype "passive"))
    )
    (net (code "64") (name "Net-(IC7-O2)") (class "Default")
      (node (ref "IC7") (pin "17") (pinfunction "O2_17") (pintype "open_collector"))
      (node (ref "R53") (pin "1") (pinfunction "1_1") (pintype "passive"))
      (node (ref "T1") (pin "4") (pinfunction "G_4") (pintype "passive"))
    )
    (net (code "65") (name "Net-(IC7-O3)") (class "Default")
      (node (ref "IC7") (pin "16") (pinfunction "O3_16") (pintype "open_collector"))
      (node (ref "R52") (pin "1") (pinfunction "1_1") (pintype "passive"))
      (node (ref "T2") (pin "2") (pinfunction "G_2") (pintype "passive"))
    )
    (net (code "66") (name "Net-(IC7-O4)") (class "Default")
      (node (ref "IC7") (pin "15") (pinfunction "O4_15") (pintype "open_collector"))
      (node (ref "R51") (pin "1") (pinfunction "1_1") (pintype "passive"))
      (node (ref "T2") (pin "4") (pinfunction "G_4") (pintype "passive"))
    )
    (net (code "67") (name "Net-(IC7-O5)") (class "Default")
      (node (ref "IC7") (pin "14") (pinfunction "O5_14") (pintype "open_collector"))
      (node (ref "R50") (pin "1") (pinfunction "1_1") (pintype "passive"))
      (node (ref "T3") (pin "2") (pinfunction "G_2") (pintype "passive"))
    )
    (net (code "68") (name "Net-(IC7-O6)") (class "Default")
      (node (ref "IC7") (pin "13") (pinfunction "O6_13") (pintype "open_collector"))
      (node (ref "R49") (pin "1") (pinfunction "1_1") (pintype "passive"))
      (node (ref "T3") (pin "4") (pinfunction "G_4") (pintype "passive"))
    )
    (net (code "69") (name "Net-(IC7-O7)") (class "Default")
      (node (ref "IC7") (pin "12") (pinfunction "O7_12") (pintype "open_collector"))
      (node (ref "R46") (pin "1") (pinfunction "1_1") (pintype "passive"))
      (node (ref "T4") (pin "2") (pinfunction "G_2") (pintype "passive"))
    )
    (net (code "70") (name "Net-(IC7-O8)") (class "Default")
      (node (ref "IC7") (pin "11") (pinfunction "O8_11") (pintype "open_collector"))
      (node (ref "R45") (pin "1") (pinfunction "1_1") (pintype "passive"))
      (node (ref "T4") (pin "4") (pinfunction "G_4") (pintype "passive"))
    )
    (net (code "71") (name "Net-(JP1-Pad1)") (class "Default")
      (node (ref "JP1") (pin "1") (pinfunction "1_1") (pintype "passive"))
      (node (ref "R1") (pin "1") (pinfunction "1_1") (pintype "passive"))
      (node (ref "R7") (pin "1") (pinfunction "1_1") (pintype "passive"))
    )
    (net (code "72") (name "Net-(JP2-Pad1)") (class "Default")
      (node (ref "JP2") (pin "1") (pinfunction "1_1") (pintype "passive"))
      (node (ref "R2") (pin "1") (pinfunction "1_1") (pintype "passive"))
      (node (ref "R9") (pin "1") (pinfunction "1_1") (pintype "passive"))
    )
    (net (code "73") (name "Net-(JP3-Pad1)") (class "Default")
      (node (ref "JP3") (pin "1") (pinfunction "1_1") (pintype "passive"))
      (node (ref "R11") (pin "1") (pinfunction "1_1") (pintype "passive"))
      (node (ref "R3") (pin "1") (pinfunction "1_1") (pintype "passive"))
    )
    (net (code "74") (name "Net-(JP4-Pad1)") (class "Default")
      (node (ref "JP4") (pin "1") (pinfunction "1_1") (pintype "passive"))
      (node (ref "R34") (pin "1") (pinfunction "1_1") (pintype "passive"))
      (node (ref "R36") (pin "1") (pinfunction "1_1") (pintype "passive"))
    )
    (net (code "75") (name "Net-(T1A-D)") (class "Default")
      (node (ref "D16") (pin "C") (pinfunction "C_C") (pintype "passive"))
      (node (ref "T1") (pin "7") (pinfunction "D_7") (pintype "passive"))
      (node (ref "X5") (pin "8") (pinfunction "K_8") (pintype "passive"))
    )
    (net (code "76") (name "Net-(T1B-D)") (class "Default")
      (node (ref "D14") (pin "C") (pinfunction "C_C") (pintype "passive"))
      (node (ref "T1") (pin "6") (pinfunction "D_6") (pintype "passive"))
      (node (ref "X5") (pin "7") (pinfunction "K_7") (pintype "passive"))
    )
    (net (code "77") (name "Net-(T2A-D)") (class "Default")
      (node (ref "T2") (pin "7") (pinfunction "D_7") (pintype "passive"))
      (node (ref "X5") (pin "6") (pinfunction "K_6") (pintype "passive"))
    )
    (net (code "78") (name "Net-(T2B-D)") (class "Default")
      (node (ref "D11") (pin "C") (pinfunction "C_C") (pintype "passive"))
      (node (ref "T2") (pin "6") (pinfunction "D_6") (pintype "passive"))
      (node (ref "X5") (pin "5") (pinfunction "K_5") (pintype "passive"))
    )
    (net (code "79") (name "Net-(T3A-D)") (class "Default")
      (node (ref "D9") (pin "C") (pinfunction "C_C") (pintype "passive"))
      (node (ref "T3") (pin "7") (pinfunction "D_7") (pintype "passive"))
      (node (ref "X5") (pin "4") (pinfunction "K_4") (pintype "passive"))
    )
    (net (code "80") (name "Net-(T3B-D)") (class "Default")
      (node (ref "D7") (pin "C") (pinfunction "C_C") (pintype "passive"))
      (node (ref "T3") (pin "6") (pinfunction "D_6") (pintype "passive"))
      (node (ref "X5") (pin "3") (pinfunction "K_3") (pintype "passive"))
    )
    (net (code "81") (name "Net-(T4A-D)") (class "Default")
      (node (ref "D5") (pin "C") (pinfunction "C_C") (pintype "passive"))
      (node (ref "T4") (pin "7") (pinfunction "D_7") (pintype "passive"))
      (node (ref "X5") (pin "2") (pinfunction "K_2") (pintype "passive"))
    )
    (net (code "82") (name "Net-(T4B-D)") (class "Default")
      (node (ref "D3") (pin "C") (pinfunction "C_C") (pintype "passive"))
      (node (ref "T4") (pin "6") (pinfunction "D_6") (pintype "passive"))
      (node (ref "X5") (pin "1") (pinfunction "K_1") (pintype "passive"))
    )
    (net (code "83") (name "Net-(U$2-A0)") (class "Default")
      (node (ref "R47") (pin "1") (pinfunction "1_1") (pintype "passive"))
      (node (ref "SJ4") (pin "2") (pinfunction "2_2") (pintype "passive"))
      (node (ref "U$2") (pin "7") (pinfunction "A0_7") (pintype "input"))
    )
    (net (code "84") (name "Net-(U$2-A1)") (class "Default")
      (node (ref "R48") (pin "1") (pinfunction "1_1") (pintype "passive"))
      (node (ref "SJ5") (pin "2") (pinfunction "2_2") (pintype "passive"))
      (node (ref "U$2") (pin "8") (pinfunction "A1_8") (pintype "input"))
    )
    (net (code "85") (name "Net-(U$3-A1)") (class "Default")
      (node (ref "R55") (pin "2") (pinfunction "2_2") (pintype "passive"))
      (node (ref "U$3") (pin "1") (pinfunction "A1_1") (pintype "input"))
    )
    (net (code "86") (name "Net-(U$3-A2)") (class "Default")
      (node (ref "R56") (pin "2") (pinfunction "2_2") (pintype "passive"))
      (node (ref "U$3") (pin "3") (pinfunction "A2_3") (pintype "input"))
    )
    (net (code "87") (name "Net-(U$3-A3)") (class "Default")
      (node (ref "R57") (pin "2") (pinfunction "2_2") (pintype "passive"))
      (node (ref "U$3") (pin "5") (pinfunction "A3_5") (pintype "input"))
    )
    (net (code "88") (name "Net-(U$3-A4)") (class "Default")
      (node (ref "R58") (pin "2") (pinfunction "2_2") (pintype "passive"))
      (node (ref "U$3") (pin "7") (pinfunction "A4_7") (pintype "input"))
    )
    (net (code "89") (name "Net-(U$4-A1)") (class "Default")
      (node (ref "R59") (pin "2") (pinfunction "2_2") (pintype "passive"))
      (node (ref "U$4") (pin "1") (pinfunction "A1_1") (pintype "input"))
    )
    (net (code "90") (name "Net-(U$4-A2)") (class "Default")
      (node (ref "R60") (pin "2") (pinfunction "2_2") (pintype "passive"))
      (node (ref "U$4") (pin "3") (pinfunction "A2_3") (pintype "input"))
    )
    (net (code "91") (name "Net-(U$4-A3)") (class "Default")
      (node (ref "R61") (pin "2") (pinfunction "2_2") (pintype "passive"))
      (node (ref "U$4") (pin "5") (pinfunction "A3_5") (pintype "input"))
    )
    (net (code "92") (name "Net-(U$4-A4)") (class "Default")
      (node (ref "R62") (pin "2") (pinfunction "2_2") (pintype "passive"))
      (node (ref "U$4") (pin "7") (pinfunction "A4_7") (pintype "input"))
    )
    (net (code "93") (name "Net-(X1A-KL)") (class "Default")
      (node (ref "ULN3") (pin "11") (pinfunction "11_11") (pintype "bidirectional"))
      (node (ref "X1") (pin "1") (pinfunction "KL_1") (pintype "passive"))
    )
    (net (code "94") (name "Net-(X1C-KL)") (class "Default")
      (node (ref "ULN3") (pin "12") (pinfunction "12_12") (pintype "bidirectional"))
      (node (ref "X1") (pin "3") (pinfunction "KL_3") (pintype "passive"))
    )
    (net (code "95") (name "Net-(X1E-KL)") (class "Default")
      (node (ref "ULN3") (pin "13") (pinfunction "13_13") (pintype "bidirectional"))
      (node (ref "X1") (pin "5") (pinfunction "KL_5") (pintype "passive"))
    )
    (net (code "96") (name "Net-(X1G-KL)") (class "Default")
      (node (ref "ULN3") (pin "14") (pinfunction "14_14") (pintype "bidirectional"))
      (node (ref "X1") (pin "7") (pinfunction "KL_7") (pintype "passive"))
    )
    (net (code "97") (name "Net-(X6A-K)") (class "Default")
      (node (ref "R62") (pin "1") (pinfunction "1_1") (pintype "passive"))
      (node (ref "X6") (pin "1") (pinfunction "K_1") (pintype "passive"))
    )
    (net (code "98") (name "Net-(X6B-K)") (class "Default")
      (node (ref "R61") (pin "1") (pinfunction "1_1") (pintype "passive"))
      (node (ref "X6") (pin "2") (pinfunction "K_2") (pintype "passive"))
    )
    (net (code "99") (name "Net-(X6C-K)") (class "Default")
      (node (ref "R60") (pin "1") (pinfunction "1_1") (pintype "passive"))
      (node (ref "X6") (pin "3") (pinfunction "K_3") (pintype "passive"))
    )
    (net (code "100") (name "Net-(X6D-K)") (class "Default")
      (node (ref "R59") (pin "1") (pinfunction "1_1") (pintype "passive"))
      (node (ref "X6") (pin "4") (pinfunction "K_4") (pintype "passive"))
    )
    (net (code "101") (name "Net-(X6E-K)") (class "Default")
      (node (ref "R58") (pin "1") (pinfunction "1_1") (pintype "passive"))
      (node (ref "X6") (pin "5") (pinfunction "K_5") (pintype "passive"))
    )
    (net (code "102") (name "Net-(X6F-K)") (class "Default")
      (node (ref "R57") (pin "1") (pinfunction "1_1") (pintype "passive"))
      (node (ref "X6") (pin "6") (pinfunction "K_6") (pintype "passive"))
    )
    (net (code "103") (name "Net-(X6G-K)") (class "Default")
      (node (ref "R56") (pin "1") (pinfunction "1_1") (pintype "passive"))
      (node (ref "X6") (pin "7") (pinfunction "K_7") (pintype "passive"))
    )
    (net (code "104") (name "Net-(X6H-K)") (class "Default")
      (node (ref "R55") (pin "1") (pinfunction "1_1") (pintype "passive"))
      (node (ref "X6") (pin "8") (pinfunction "K_8") (pintype "passive"))
    )
    (net (code "105") (name "PT100-1") (class "Default")
      (node (ref "C10") (pin "1") (pinfunction "1_1") (pintype "passive"))
      (node (ref "R31") (pin "1") (pinfunction "1_1") (pintype "passive"))
      (node (ref "U$2") (pin "16") (pinfunction "IN0_16") (pintype "input"))
    )
    (net (code "106") (name "PT100-2") (class "Default")
      (node (ref "C11") (pin "1") (pinfunction "1_1") (pintype "passive"))
      (node (ref "R32") (pin "1") (pinfunction "1_1") (pintype "passive"))
      (node (ref "U$2") (pin "15") (pinfunction "IN1_15") (pintype "input"))
    )
    (net (code "107") (name "PT100-3") (class "Default")
      (node (ref "C12") (pin "1") (pinfunction "1_1") (pintype "passive"))
      (node (ref "R33") (pin "1") (pinfunction "1_1") (pintype "passive"))
      (node (ref "U$2") (pin "14") (pinfunction "IN2_14") (pintype "input"))
    )
    (net (code "108") (name "PT100-4") (class "Default")
      (node (ref "C15") (pin "1") (pinfunction "1_1") (pintype "passive"))
      (node (ref "R44") (pin "1") (pinfunction "1_1") (pintype "passive"))
      (node (ref "U$2") (pin "13") (pinfunction "IN3_13") (pintype "input"))
    )
    (net (code "109") (name "PWM_1") (class "Default")
      (node (ref "SV2") (pin "4") (pinfunction "4_4") (pintype "passive"))
      (node (ref "ULN3") (pin "5") (pinfunction "5_5") (pintype "bidirectional"))
    )
    (net (code "110") (name "PWM_2") (class "Default")
      (node (ref "SV2") (pin "3") (pinfunction "3_3") (pintype "passive"))
      (node (ref "ULN3") (pin "6") (pinfunction "6_6") (pintype "bidirectional"))
    )
    (net (code "111") (name "PWM_3") (class "Default")
      (node (ref "SV2") (pin "2") (pinfunction "2_2") (pintype "passive"))
      (node (ref "ULN3") (pin "7") (pinfunction "7_7") (pintype "bidirectional"))
    )
    (net (code "112") (name "PWM_4") (class "Default")
      (node (ref "SV2") (pin "1") (pinfunction "1_1") (pintype "passive"))
      (node (ref "ULN3") (pin "8") (pinfunction "8_8") (pintype "bidirectional"))
    )
    (net (code "113") (name "SCL") (class "Default")
      (node (ref "IC6") (pin "12") (pinfunction "SCL_12") (pintype "input"))
      (node (ref "SV2") (pin "14") (pinfunction "14_14") (pintype "passive"))
      (node (ref "U$2") (pin "3") (pinfunction "SCL_3") (pintype "input"))
    )
    (net (code "114") (name "SDA") (class "Default")
      (node (ref "IC6") (pin "13") (pinfunction "SDA_13") (pintype "bidirectional"))
      (node (ref "SV2") (pin "13") (pinfunction "13_13") (pintype "passive"))
      (node (ref "U$2") (pin "2") (pinfunction "SDA_2") (pintype "bidirectional"))
    )
    (net (code "115") (name "V+12-24VV") (class "Default")
      (node (ref "D12") (pin "C") (pinfunction "C_C") (pintype "passive"))
      (node (ref "R45") (pin "2") (pinfunction "2_2") (pintype "passive"))
      (node (ref "R46") (pin "2") (pinfunction "2_2") (pintype "passive"))
      (node (ref "R49") (pin "2") (pinfunction "2_2") (pintype "passive"))
      (node (ref "R50") (pin "2") (pinfunction "2_2") (pintype "passive"))
      (node (ref "R51") (pin "2") (pinfunction "2_2") (pintype "passive"))
      (node (ref "R52") (pin "2") (pinfunction "2_2") (pintype "passive"))
      (node (ref "R53") (pin "2") (pinfunction "2_2") (pintype "passive"))
      (node (ref "R54") (pin "2") (pinfunction "2_2") (pintype "passive"))
      (node (ref "T1") (pin "1") (pinfunction "S_1") (pintype "passive"))
      (node (ref "T1") (pin "3") (pinfunction "S_3") (pintype "passive"))
      (node (ref "T2") (pin "1") (pinfunction "S_1") (pintype "passive"))
      (node (ref "T2") (pin "3") (pinfunction "S_3") (pintype "passive"))
      (node (ref "T3") (pin "1") (pinfunction "S_1") (pintype "passive"))
      (node (ref "T3") (pin "3") (pinfunction "S_3") (pintype "passive"))
      (node (ref "T4") (pin "1") (pinfunction "S_1") (pintype "passive"))
      (node (ref "T4") (pin "3") (pinfunction "S_3") (pintype "passive"))
      (node (ref "X5") (pin "9") (pinfunction "K_9") (pintype "passive"))
    )
    (net (code "116") (name "VCC") (class "Default")
      (node (ref "C1") (pin "1") (pinfunction "1_1") (pintype "passive"))
      (node (ref "C16") (pin "2") (pinfunction "2_2") (pintype "passive"))
      (node (ref "C19") (pin "1") (pinfunction "1_1") (pintype "passive"))
      (node (ref "C2") (pin "1") (pinfunction "1_1") (pintype "passive"))
      (node (ref "IC2") (pin "4") (pinfunction "V+_4") (pintype "power_in"))
      (node (ref "R47") (pin "2") (pinfunction "2_2") (pintype "passive"))
      (node (ref "R48") (pin "2") (pinfunction "2_2") (pintype "passive"))
      (node (ref "U$1") (pin "3") (pinfunction "EN_3") (pintype "bidirectional"))
      (node (ref "U$1") (pin "4") (pinfunction "VIN_4") (pintype "bidirectional"))
      (node (ref "U$2") (pin "5") (pinfunction "VCC_5") (pintype "power_in"))
      (node (ref "ULN3") (pin "10") (pinfunction "10_10") (pintype "bidirectional"))
      (node (ref "X1") (pin "2") (pinfunction "KL_2") (pintype "passive"))
      (node (ref "X1") (pin "4") (pinfunction "KL_4") (pintype "passive"))
      (node (ref "X1") (pin "6") (pinfunction "KL_6") (pintype "passive"))
      (node (ref "X1") (pin "8") (pinfunction "KL_8") (pintype "passive"))
    )
    (net (code "117") (name "VREF") (class "Default")
      (node (ref "C9") (pin "1") (pinfunction "1_1") (pintype "passive"))
      (node (ref "IC1") (pin "5") (pinfunction "IN+_5") (pintype "input"))
      (node (ref "IC2") (pin "5") (pinfunction "IN+_5") (pintype "input"))
      (node (ref "IC3") (pin "5") (pinfunction "IN+_5") (pintype "input"))
      (node (ref "IC4") (pin "5") (pinfunction "IN+_5") (pintype "input"))
      (node (ref "U$1") (pin "5") (pinfunction "VOUT_5") (pintype "bidirectional"))
    )
    (net (code "118") (name "unconnected-(IC6-INTB-Pad19)") (class "Default")
      (node (ref "IC6") (pin "19") (pinfunction "INTB_19") (pintype "output"))
    )
    (net (code "119") (name "unconnected-(IC6-~{RESET}-Pad18)") (class "Default")
      (node (ref "IC6") (pin "18") (pinfunction "~{RESET}_18") (pintype "input"))
    )
    (net (code "120") (name "unconnected-(IC7-CD+-Pad10)") (class "Default")
      (node (ref "IC7") (pin "10") (pinfunction "CD+_10") (pintype "passive"))
    )
    (net (code "121") (name "unconnected-(T1A-D2-Pad8)") (class "Default")
      (node (ref "T1") (pin "8") (pinfunction "D2_8") (pintype "passive"))
    )
    (net (code "122") (name "unconnected-(T1B-D2-Pad5)") (class "Default")
      (node (ref "T1") (pin "5") (pinfunction "D2_5") (pintype "passive"))
    )
    (net (code "123") (name "unconnected-(T2A-D2-Pad8)") (class "Default")
      (node (ref "T2") (pin "8") (pinfunction "D2_8") (pintype "passive"))
    )
    (net (code "124") (name "unconnected-(T2B-D2-Pad5)") (class "Default")
      (node (ref "T2") (pin "5") (pinfunction "D2_5") (pintype "passive"))
    )
    (net (code "125") (name "unconnected-(T3A-D2-Pad8)") (class "Default")
      (node (ref "T3") (pin "8") (pinfunction "D2_8") (pintype "passive"))
    )
    (net (code "126") (name "unconnected-(T3B-D2-Pad5)") (class "Default")
      (node (ref "T3") (pin "5") (pinfunction "D2_5") (pintype "passive"))
    )
    (net (code "127") (name "unconnected-(T4A-D2-Pad8)") (class "Default")
      (node (ref "T4") (pin "8") (pinfunction "D2_8") (pintype "passive"))
    )
    (net (code "128") (name "unconnected-(T4B-D2-Pad5)") (class "Default")
      (node (ref "T4") (pin "5") (pinfunction "D2_5") (pintype "passive"))
    )
    (net (code "129") (name "unconnected-(U$2-IN4-Pad12)") (class "Default")
      (node (ref "U$2") (pin "12") (pinfunction "IN4_12") (pintype "input"))
    )
    (net (code "130") (name "unconnected-(U$2-IN5-Pad11)") (class "Default")
      (node (ref "U$2") (pin "11") (pinfunction "IN5_11") (pintype "input"))
    )
    (net (code "131") (name "unconnected-(U$2-IN6-Pad10)") (class "Default")
      (node (ref "U$2") (pin "10") (pinfunction "IN6_10") (pintype "input"))
    )
    (net (code "132") (name "unconnected-(U$2-IN7-Pad9)") (class "Default")
      (node (ref "U$2") (pin "9") (pinfunction "IN7_9") (pintype "input"))
    )
    (net (code "133") (name "unconnected-(U$2-{slash}INT-Pad6)") (class "Default")
      (node (ref "U$2") (pin "6") (pinfunction "/INT_6") (pintype "output"))
    )
    (net (code "134") (name "unconnected-(ULN3-Pad1)") (class "Default")
      (node (ref "ULN3") (pin "1") (pinfunction "1_1") (pintype "bidirectional"))
    )
    (net (code "135") (name "unconnected-(ULN3-Pad2)") (class "Default")
      (node (ref "ULN3") (pin "2") (pinfunction "2_2") (pintype "bidirectional"))
    )
    (net (code "136") (name "unconnected-(ULN3-Pad3)") (class "Default")
      (node (ref "ULN3") (pin "3") (pinfunction "3_3") (pintype "bidirectional"))
    )
    (net (code "137") (name "unconnected-(ULN3-Pad4)") (class "Default")
      (node (ref "ULN3") (pin "4") (pinfunction "4_4") (pintype "bidirectional"))
    )
    (net (code "138") (name "unconnected-(ULN3-Pad15)") (class "Default")
      (node (ref "ULN3") (pin "15") (pinfunction "15_15") (pintype "bidirectional"))
    )
    (net (code "139") (name "unconnected-(ULN3-Pad16)") (class "Default")
      (node (ref "ULN3") (pin "16") (pinfunction "16_16") (pintype "bidirectional"))
    )
    (net (code "140") (name "unconnected-(ULN3-Pad17)") (class "Default")
      (node (ref "ULN3") (pin "17") (pinfunction "17_17") (pintype "bidirectional"))
    )
    (net (code "141") (name "unconnected-(ULN3-Pad18)") (class "Default")
      (node (ref "ULN3") (pin "18") (pinfunction "18_18") (pintype "bidirectional"))
    )
    (net (code "142") (name "unconnected-(X1I-KL-Pad9)") (class "Default")
      (node (ref "X1") (pin "9") (pinfunction "KL_9") (pintype "passive"))
    )
  )
)
